# C8T6_MINI.net
KiCad netlist of a schematic drawn in Altium Designer
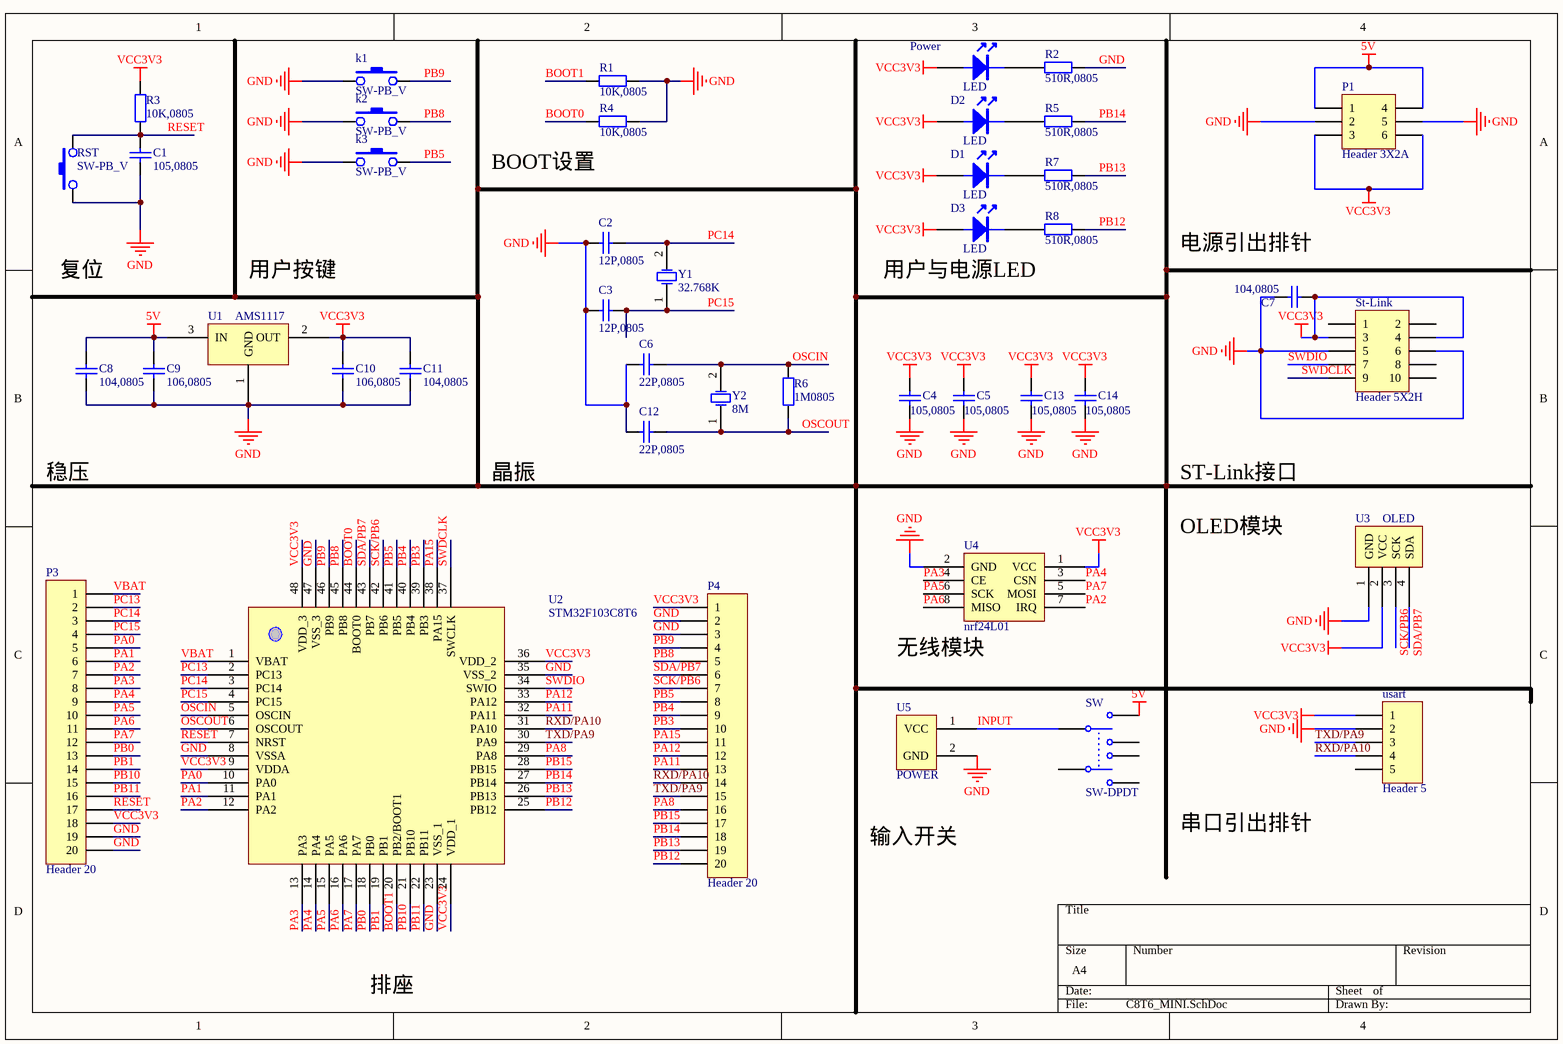
[diagram p0: C8T6_MINI.SchDoc]

(export (version "E")
  (design (tool "Eeschema 10.0.6"))
  (components
    (comp (ref "C1")
      (value "105,0805")
      (footprint "6-0805_M")
      (description "Capacitor")
      (fields (field (name "PUBLISHER") "Altium Limited"))
      (libsource (lib "STM32F103C8T6") (part "Cap"))
    )
    (comp (ref "C2")
      (value "12P,0805")
      (footprint "6-0805_N")
      (description "Capacitor")
      (fields (field (name "PUBLISHER") "Altium Limited"))
      (libsource (lib "stm32") (part "Cap_2"))
    )
    (comp (ref "C3")
      (value "12P,0805")
      (footprint "6-0805_N")
      (description "Capacitor")
      (fields (field (name "PUBLISHER") "Altium Limited"))
      (libsource (lib "stm32") (part "Cap_2"))
    )
    (comp (ref "C4")
      (value "105,0805")
      (footprint "6-0805_N")
      (description "Capacitor")
      (fields (field (name "PUBLISHER") "Altium Limited"))
      (libsource (lib "stm32") (part "Cap_2"))
    )
    (comp (ref "C5")
      (value "105,0805")
      (footprint "6-0805_N")
      (description "Capacitor")
      (fields (field (name "PUBLISHER") "Altium Limited"))
      (libsource (lib "stm32") (part "Cap_2"))
    )
    (comp (ref "C6")
      (value "22P,0805")
      (footprint "6-0805_N")
      (description "Capacitor")
      (fields (field (name "PUBLISHER") "Altium Limited"))
      (libsource (lib "stm32") (part "Cap_2"))
    )
    (comp (ref "C7")
      (value "104,0805")
      (footprint "6-0805_N")
      (description "Capacitor")
      (fields (field (name "PUBLISHER") "Altium Limited"))
      (libsource (lib "stm32") (part "Cap_2"))
    )
    (comp (ref "C8")
      (value "104,0805")
      (footprint "6-0805_N")
      (description "Capacitor")
      (fields (field (name "PUBLISHER") "Altium Limited"))
      (libsource (lib "stm32") (part "Cap_2"))
    )
    (comp (ref "C9")
      (value "106,0805")
      (footprint "6-0805_N")
      (description "Capacitor")
      (fields (field (name "PUBLISHER") "Altium Limited"))
      (libsource (lib "stm32") (part "Cap_2"))
    )
    (comp (ref "C10")
      (value "106,0805")
      (footprint "6-0805_N")
      (description "Capacitor")
      (fields (field (name "PUBLISHER") "Altium Limited"))
      (libsource (lib "stm32") (part "Cap_2"))
    )
    (comp (ref "C11")
      (value "104,0805")
      (footprint "6-0805_N")
      (description "Capacitor")
      (fields (field (name "PUBLISHER") "Altium Limited"))
      (libsource (lib "stm32") (part "Cap_2"))
    )
    (comp (ref "C12")
      (value "22P,0805")
      (footprint "6-0805_N")
      (description "Capacitor")
      (fields (field (name "PUBLISHER") "Altium Limited"))
      (libsource (lib "stm32") (part "Cap_2"))
    )
    (comp (ref "C13")
      (value "105,0805")
      (footprint "6-0805_N")
      (description "Capacitor")
      (fields (field (name "PUBLISHER") "Altium Limited"))
      (libsource (lib "stm32") (part "Cap_2"))
    )
    (comp (ref "C14")
      (value "105,0805")
      (footprint "6-0805_N")
      (description "Capacitor")
      (fields (field (name "PUBLISHER") "Altium Limited"))
      (libsource (lib "stm32") (part "Cap_2"))
    )
    (comp (ref "D1") (value "LED") (footprint "LED 0805G") (libsource (lib "STM32F103C8T6") (part "LED")))
    (comp (ref "D2") (value "LED") (footprint "LED 0805G") (libsource (lib "STM32F103C8T6") (part "LED")))
    (comp (ref "D3") (value "LED") (footprint "LED 0805G") (libsource (lib "STM32F103C8T6") (part "LED")))
    (comp (ref "k1")
      (value "SW-PB_V")
      (footprint "TSW SMD-3*6*2.5")
      (description "SWITCH")
      (libsource (lib "stm32") (part "SW-PB_V"))
    )
    (comp (ref "k2")
      (value "SW-PB_V")
      (footprint "TSW SMD-3*6*2.5")
      (description "SWITCH")
      (libsource (lib "stm32") (part "SW-PB_V"))
    )
    (comp (ref "k3")
      (value "SW-PB_V")
      (footprint "TSW SMD-3*6*2.5")
      (description "SWITCH")
      (libsource (lib "stm32") (part "SW-PB_V"))
    )
    (comp (ref "P1")
      (value "Header 3X2A")
      (footprint "HDR2X3_CEN")
      (description "Header, 3-Pin, Dual row")
      (fields (field (name "PUBLISHER") "Altium Limited"))
      (libsource (lib "Miscellaneous Connectors") (part "Header 3X2A"))
    )
    (comp (ref "P3")
      (value "Header 20")
      (footprint "HDR1X20")
      (description "Header, 20-Pin")
      (fields (field (name "PUBLISHER") "Altium Limited"))
      (libsource (lib "STM32F103C8T6") (part "Header 20"))
    )
    (comp (ref "P4")
      (value "Header 20")
      (footprint "HDR1X20")
      (description "Header, 20-Pin")
      (fields (field (name "PUBLISHER") "Altium Limited"))
      (libsource (lib "") (part "Header 20_1"))
    )
    (comp (ref "Power") (value "LED") (footprint "LED 0805G") (libsource (lib "STM32F103C8T6") (part "LED")))
    (comp (ref "R1")
      (value "10K,0805")
      (footprint "6-0805_N")
      (description "Resistor")
      (fields (field (name "PUBLISHER") "Altium Limited"))
      (libsource (lib "STM32F103C8T6") (part "Res2"))
    )
    (comp (ref "R2")
      (value "510R,0805")
      (footprint "6-0805_N")
      (description "Resistor")
      (fields (field (name "PUBLISHER") "Altium Limited"))
      (libsource (lib "STM32F103C8T6") (part "Res2"))
    )
    (comp (ref "R3")
      (value "10K,0805")
      (footprint "6-0805_N")
      (description "Resistor")
      (fields (field (name "PUBLISHER") "Altium Limited"))
      (libsource (lib "") (part "Res2_1"))
    )
    (comp (ref "R4")
      (value "10K,0805")
      (footprint "6-0805_N")
      (description "Resistor")
      (fields (field (name "PUBLISHER") "Altium Limited"))
      (libsource (lib "STM32F103C8T6") (part "Res2"))
    )
    (comp (ref "R5")
      (value "510R,0805")
      (footprint "6-0805_N")
      (description "Resistor")
      (fields (field (name "PUBLISHER") "Altium Limited"))
      (libsource (lib "STM32F103C8T6") (part "Res2"))
    )
    (comp (ref "R6")
      (value "1M0805")
      (footprint "6-0805_N")
      (description "Resistor")
      (fields (field (name "PUBLISHER") "Altium Limited"))
      (libsource (lib "") (part "Res2_1"))
    )
    (comp (ref "R7")
      (value "510R,0805")
      (footprint "6-0805_N")
      (description "Resistor")
      (fields (field (name "PUBLISHER") "Altium Limited"))
      (libsource (lib "STM32F103C8T6") (part "Res2"))
    )
    (comp (ref "R8")
      (value "510R,0805")
      (footprint "6-0805_N")
      (description "Resistor")
      (fields (field (name "PUBLISHER") "Altium Limited"))
      (libsource (lib "STM32F103C8T6") (part "Res2"))
    )
    (comp (ref "RST")
      (value "SW-PB_V")
      (footprint "TSW SMD-3*6*2.5")
      (description "SWITCH")
      (libsource (lib "STM32F103C8T6") (part "SW-PB_V"))
    )
    (comp (ref "St-Link")
      (value "Header 5X2H")
      (footprint "HDR2X5H")
      (description "Header, 5-Pin, Dual row, Right Angle")
      (fields (field (name "PUBLISHER") "Altium Limited"))
      (libsource (lib "Miscellaneous Connectors") (part "Header 5X2H"))
    )
    (comp (ref "SW")
      (value "SW-DPDT")
      (footprint "PCBComponent_1")
      (description "Double-Pole, Double-Throw Switch")
      (fields (field (name "PUBLISHER") "Altium Limited"))
      (libsource (lib "Miscellaneous Devices") (part "SW-DPDT"))
    )
    (comp (ref "U1")
      (value "AMS1117")
      (footprint "SOT223_M")
      (libsource (lib "AMS1117") (part "Component_1"))
    )
    (comp (ref "U2")
      (value "STM32F103C8T6")
      (footprint "TQFP48 7x7_L")
      (libsource (lib "stm32") (part "STM32F103C8T6"))
    )
    (comp (ref "U3") (value "OLED") (footprint "OLED") (libsource (lib "Schlib1") (part "oled")))
    (comp (ref "U4") (value "nrf24L01") (footprint "NRF24L01") (libsource (lib "Schlib1") (part "nrf24L01")))
    (comp (ref "U5") (value "POWER") (footprint "power") (libsource (lib "Schlib1") (part "POWER")))
    (comp (ref "usart")
      (value "Header 5")
      (footprint "HDR1X5")
      (description "Header, 5-Pin")
      (fields (field (name "PUBLISHER") "Altium Limited"))
      (libsource (lib "Miscellaneous Connectors") (part "Header 5"))
    )
    (comp (ref "Y1")
      (value "32.768K")
      (footprint "圆柱晶振")
      (description "Crystal Oscillator")
      (fields (field (name "PUBLISHER") "Altium Limited"))
      (libsource (lib "stm32") (part "XTAL_1"))
    )
    (comp (ref "Y2")
      (value "8M")
      (footprint "XTAL-49S DIP")
      (description "Crystal Oscillator")
      (fields (field (name "PUBLISHER") "Altium Limited"))
      (libsource (lib "STM32F103C8T6") (part "XTAL"))
    )
  )
  (nets
    (net (code "1") (name "/BOOT0") (class "Default")
      (node (ref "R4") (pin "1") (pinfunction "1_1") (pintype "passive"))
      (node (ref "U2") (pin "44") (pinfunction "BOOT0_44") (pintype "passive"))
    )
    (net (code "2") (name "/BOOT1") (class "Default")
      (node (ref "R1") (pin "1") (pinfunction "1_1") (pintype "passive"))
      (node (ref "U2") (pin "20") (pinfunction "PB2/BOOT1_20") (pintype "passive"))
    )
    (net (code "3") (name "/INPUT") (class "Default")
      (node (ref "SW") (pin "1") (pinfunction "1_1") (pintype "passive"))
      (node (ref "U5") (pin "1") (pinfunction "VCC_1") (pintype "passive"))
    )
    (net (code "4") (name "/OSCIN") (class "Default")
      (node (ref "C6") (pin "1") (pinfunction "1_1") (pintype "passive"))
      (node (ref "R6") (pin "2") (pinfunction "2_2") (pintype "passive"))
      (node (ref "U2") (pin "5") (pinfunction "OSCIN_5") (pintype "passive"))
      (node (ref "Y2") (pin "2") (pinfunction "OSC2_2") (pintype "passive"))
    )
    (net (code "5") (name "/OSCOUT") (class "Default")
      (node (ref "C12") (pin "1") (pinfunction "1_1") (pintype "passive"))
      (node (ref "R6") (pin "1") (pinfunction "1_1") (pintype "passive"))
      (node (ref "U2") (pin "6") (pinfunction "OSCOUT_6") (pintype "passive"))
      (node (ref "Y2") (pin "1") (pinfunction "OSC1_1") (pintype "passive"))
    )
    (net (code "6") (name "/PA0") (class "Default")
      (node (ref "P3") (pin "5") (pinfunction "5_5") (pintype "passive"))
      (node (ref "U2") (pin "10") (pinfunction "PA0_10") (pintype "passive"))
    )
    (net (code "7") (name "/PA1") (class "Default")
      (node (ref "P3") (pin "6") (pinfunction "6_6") (pintype "passive"))
      (node (ref "U2") (pin "11") (pinfunction "PA1_11") (pintype "passive"))
    )
    (net (code "8") (name "/PA2") (class "Default")
      (node (ref "P3") (pin "7") (pinfunction "7_7") (pintype "passive"))
      (node (ref "U2") (pin "12") (pinfunction "PA2_12") (pintype "passive"))
      (node (ref "U4") (pin "7") (pinfunction "IRQ_7") (pintype "passive"))
    )
    (net (code "9") (name "/PA3") (class "Default")
      (node (ref "P3") (pin "8") (pinfunction "8_8") (pintype "passive"))
      (node (ref "U2") (pin "13") (pinfunction "PA3_13") (pintype "passive"))
      (node (ref "U4") (pin "4") (pinfunction "CE_4") (pintype "passive"))
    )
    (net (code "10") (name "/PA4") (class "Default")
      (node (ref "P3") (pin "9") (pinfunction "9_9") (pintype "passive"))
      (node (ref "U2") (pin "14") (pinfunction "PA4_14") (pintype "passive"))
      (node (ref "U4") (pin "3") (pinfunction "CSN_3") (pintype "passive"))
    )
    (net (code "11") (name "/PA5") (class "Default")
      (node (ref "P3") (pin "10") (pinfunction "10_10") (pintype "passive"))
      (node (ref "U2") (pin "15") (pinfunction "PA5_15") (pintype "passive"))
      (node (ref "U4") (pin "6") (pinfunction "SCK_6") (pintype "passive"))
    )
    (net (code "12") (name "/PA6") (class "Default")
      (node (ref "P3") (pin "11") (pinfunction "11_11") (pintype "passive"))
      (node (ref "U2") (pin "16") (pinfunction "PA6_16") (pintype "passive"))
      (node (ref "U4") (pin "8") (pinfunction "MISO_8") (pintype "passive"))
    )
    (net (code "13") (name "/PA7") (class "Default")
      (node (ref "P3") (pin "12") (pinfunction "12_12") (pintype "passive"))
      (node (ref "U2") (pin "17") (pinfunction "PA7_17") (pintype "passive"))
      (node (ref "U4") (pin "5") (pinfunction "MOSI_5") (pintype "passive"))
    )
    (net (code "14") (name "/PA8") (class "Default")
      (node (ref "P4") (pin "16") (pinfunction "16_16") (pintype "passive"))
      (node (ref "U2") (pin "29") (pinfunction "PA8_29") (pintype "passive"))
    )
    (net (code "15") (name "/PA11") (class "Default")
      (node (ref "P4") (pin "13") (pinfunction "13_13") (pintype "passive"))
      (node (ref "U2") (pin "32") (pinfunction "PA11_32") (pintype "passive"))
    )
    (net (code "16") (name "/PA12") (class "Default")
      (node (ref "P4") (pin "12") (pinfunction "12_12") (pintype "passive"))
      (node (ref "U2") (pin "33") (pinfunction "PA12_33") (pintype "passive"))
    )
    (net (code "17") (name "/PA15") (class "Default")
      (node (ref "P4") (pin "11") (pinfunction "11_11") (pintype "passive"))
      (node (ref "U2") (pin "38") (pinfunction "PA15_38") (pintype "passive"))
    )
    (net (code "18") (name "/PB0") (class "Default")
      (node (ref "P3") (pin "13") (pinfunction "13_13") (pintype "passive"))
      (node (ref "U2") (pin "18") (pinfunction "PB0_18") (pintype "passive"))
    )
    (net (code "19") (name "/PB1") (class "Default")
      (node (ref "P3") (pin "14") (pinfunction "14_14") (pintype "passive"))
      (node (ref "U2") (pin "19") (pinfunction "PB1_19") (pintype "passive"))
    )
    (net (code "20") (name "/PB3") (class "Default")
      (node (ref "P4") (pin "10") (pinfunction "10_10") (pintype "passive"))
      (node (ref "U2") (pin "39") (pinfunction "PB3_39") (pintype "passive"))
    )
    (net (code "21") (name "/PB4") (class "Default")
      (node (ref "P4") (pin "9") (pinfunction "9_9") (pintype "passive"))
      (node (ref "U2") (pin "40") (pinfunction "PB4_40") (pintype "passive"))
    )
    (net (code "22") (name "/PB5") (class "Default")
      (node (ref "P4") (pin "8") (pinfunction "8_8") (pintype "passive"))
      (node (ref "U2") (pin "41") (pinfunction "PB5_41") (pintype "passive"))
      (node (ref "k3") (pin "2") (pinfunction "2_2") (pintype "passive"))
    )
    (net (code "23") (name "/PB8") (class "Default")
      (node (ref "P4") (pin "5") (pinfunction "5_5") (pintype "passive"))
      (node (ref "U2") (pin "45") (pinfunction "PB8_45") (pintype "passive"))
      (node (ref "k2") (pin "2") (pinfunction "2_2") (pintype "passive"))
    )
    (net (code "24") (name "/PB9") (class "Default")
      (node (ref "P4") (pin "4") (pinfunction "4_4") (pintype "passive"))
      (node (ref "U2") (pin "46") (pinfunction "PB9_46") (pintype "passive"))
      (node (ref "k1") (pin "2") (pinfunction "2_2") (pintype "passive"))
    )
    (net (code "25") (name "/PB10") (class "Default")
      (node (ref "P3") (pin "15") (pinfunction "15_15") (pintype "passive"))
      (node (ref "U2") (pin "21") (pinfunction "PB10_21") (pintype "passive"))
    )
    (net (code "26") (name "/PB11") (class "Default")
      (node (ref "P3") (pin "16") (pinfunction "16_16") (pintype "passive"))
      (node (ref "U2") (pin "22") (pinfunction "PB11_22") (pintype "passive"))
    )
    (net (code "27") (name "/PB12") (class "Default")
      (node (ref "P4") (pin "20") (pinfunction "20_20") (pintype "passive"))
      (node (ref "R8") (pin "2") (pinfunction "2_2") (pintype "passive"))
      (node (ref "U2") (pin "25") (pinfunction "PB12_25") (pintype "passive"))
    )
    (net (code "28") (name "/PB13") (class "Default")
      (node (ref "P4") (pin "19") (pinfunction "19_19") (pintype "passive"))
      (node (ref "R7") (pin "2") (pinfunction "2_2") (pintype "passive"))
      (node (ref "U2") (pin "26") (pinfunction "PB13_26") (pintype "passive"))
    )
    (net (code "29") (name "/PB14") (class "Default")
      (node (ref "P4") (pin "18") (pinfunction "18_18") (pintype "passive"))
      (node (ref "R5") (pin "2") (pinfunction "2_2") (pintype "passive"))
      (node (ref "U2") (pin "27") (pinfunction "PB14_27") (pintype "passive"))
    )
    (net (code "30") (name "/PB15") (class "Default")
      (node (ref "P4") (pin "17") (pinfunction "17_17") (pintype "passive"))
      (node (ref "U2") (pin "28") (pinfunction "PB15_28") (pintype "passive"))
    )
    (net (code "31") (name "/PC13") (class "Default")
      (node (ref "P3") (pin "2") (pinfunction "2_2") (pintype "passive"))
      (node (ref "U2") (pin "2") (pinfunction "PC13_2") (pintype "passive"))
    )
    (net (code "32") (name "/PC14") (class "Default")
      (node (ref "C2") (pin "1") (pinfunction "1_1") (pintype "passive"))
      (node (ref "P3") (pin "3") (pinfunction "3_3") (pintype "passive"))
      (node (ref "U2") (pin "3") (pinfunction "PC14_3") (pintype "passive"))
      (node (ref "Y1") (pin "2") (pinfunction "OSC2_2") (pintype "passive"))
    )
    (net (code "33") (name "/PC15") (class "Default")
      (node (ref "C3") (pin "1") (pinfunction "1_1") (pintype "passive"))
      (node (ref "P3") (pin "4") (pinfunction "4_4") (pintype "passive"))
      (node (ref "U2") (pin "4") (pinfunction "PC15_4") (pintype "passive"))
      (node (ref "Y1") (pin "1") (pinfunction "OSC1_1") (pintype "passive"))
    )
    (net (code "34") (name "/RESET") (class "Default")
      (node (ref "C1") (pin "2") (pinfunction "2_2") (pintype "passive"))
      (node (ref "P3") (pin "17") (pinfunction "17_17") (pintype "passive"))
      (node (ref "R3") (pin "1") (pinfunction "1_1") (pintype "passive"))
      (node (ref "RST") (pin "2") (pinfunction "2_2") (pintype "passive"))
      (node (ref "U2") (pin "7") (pinfunction "NRST_7") (pintype "passive"))
    )
    (net (code "35") (name "/RXD{slash}PA10") (class "Default")
      (node (ref "P4") (pin "14") (pinfunction "14_14") (pintype "passive"))
      (node (ref "U2") (pin "31") (pinfunction "PA10_31") (pintype "passive"))
      (node (ref "usart") (pin "4") (pinfunction "4_4") (pintype "passive"))
    )
    (net (code "36") (name "/SCK{slash}PB6") (class "Default")
      (node (ref "P4") (pin "7") (pinfunction "7_7") (pintype "passive"))
      (node (ref "U2") (pin "42") (pinfunction "PB6_42") (pintype "passive"))
      (node (ref "U3") (pin "3") (pinfunction "SCK_3") (pintype "passive"))
    )
    (net (code "37") (name "/SDA{slash}PB7") (class "Default")
      (node (ref "P4") (pin "6") (pinfunction "6_6") (pintype "passive"))
      (node (ref "U2") (pin "43") (pinfunction "PB7_43") (pintype "passive"))
      (node (ref "U3") (pin "4") (pinfunction "SDA_4") (pintype "passive"))
    )
    (net (code "38") (name "/SWDCLK") (class "Default")
      (node (ref "St-Link") (pin "9") (pinfunction "9_9") (pintype "passive"))
      (node (ref "U2") (pin "37") (pinfunction "SWCLK_37") (pintype "passive"))
    )
    (net (code "39") (name "/SWDIO") (class "Default")
      (node (ref "St-Link") (pin "7") (pinfunction "7_7") (pintype "passive"))
      (node (ref "U2") (pin "34") (pinfunction "SWIO_34") (pintype "passive"))
    )
    (net (code "40") (name "/TXD{slash}PA9") (class "Default")
      (node (ref "P4") (pin "15") (pinfunction "15_15") (pintype "passive"))
      (node (ref "U2") (pin "30") (pinfunction "PA9_30") (pintype "passive"))
      (node (ref "usart") (pin "3") (pinfunction "3_3") (pintype "passive"))
    )
    (net (code "41") (name "/VBAT") (class "Default")
      (node (ref "P3") (pin "1") (pinfunction "1_1") (pintype "passive"))
      (node (ref "U2") (pin "1") (pinfunction "VBAT_1") (pintype "passive"))
    )
    (net (code "42") (name "5V") (class "Default")
      (node (ref "C8") (pin "1") (pinfunction "1_1") (pintype "passive"))
      (node (ref "C9") (pin "1") (pinfunction "1_1") (pintype "passive"))
      (node (ref "P1") (pin "1") (pinfunction "1_1") (pintype "passive"))
      (node (ref "P1") (pin "4") (pinfunction "4_4") (pintype "passive"))
      (node (ref "SW") (pin "2") (pinfunction "2_2") (pintype "passive"))
      (node (ref "U1") (pin "3") (pinfunction "IN_3") (pintype "passive"))
    )
    (net (code "43") (name "GND") (class "Default")
      (node (ref "C1") (pin "1") (pinfunction "1_1") (pintype "passive"))
      (node (ref "C10") (pin "1") (pinfunction "1_1") (pintype "passive"))
      (node (ref "C11") (pin "1") (pinfunction "1_1") (pintype "passive"))
      (node (ref "C12") (pin "2") (pinfunction "2_2") (pintype "passive"))
      (node (ref "C13") (pin "1") (pinfunction "1_1") (pintype "passive"))
      (node (ref "C14") (pin "1") (pinfunction "1_1") (pintype "passive"))
      (node (ref "C2") (pin "2") (pinfunction "2_2") (pintype "passive"))
      (node (ref "C3") (pin "2") (pinfunction "2_2") (pintype "passive"))
      (node (ref "C4") (pin "1") (pinfunction "1_1") (pintype "passive"))
      (node (ref "C5") (pin "1") (pinfunction "1_1") (pintype "passive"))
      (node (ref "C6") (pin "2") (pinfunction "2_2") (pintype "passive"))
      (node (ref "C7") (pin "2") (pinfunction "2_2") (pintype "passive"))
      (node (ref "C8") (pin "2") (pinfunction "2_2") (pintype "passive"))
      (node (ref "C9") (pin "2") (pinfunction "2_2") (pintype "passive"))
      (node (ref "P1") (pin "2") (pinfunction "2_2") (pintype "passive"))
      (node (ref "P1") (pin "5") (pinfunction "5_5") (pintype "passive"))
      (node (ref "P3") (pin "19") (pinfunction "19_19") (pintype "passive"))
      (node (ref "P3") (pin "20") (pinfunction "20_20") (pintype "passive"))
      (node (ref "P4") (pin "2") (pinfunction "2_2") (pintype "passive"))
      (node (ref "P4") (pin "3") (pinfunction "3_3") (pintype "passive"))
      (node (ref "R1") (pin "2") (pinfunction "2_2") (pintype "passive"))
      (node (ref "R2") (pin "2") (pinfunction "2_2") (pintype "passive"))
      (node (ref "R4") (pin "2") (pinfunction "2_2") (pintype "passive"))
      (node (ref "RST") (pin "1") (pinfunction "1_1") (pintype "passive"))
      (node (ref "St-Link") (pin "5") (pinfunction "5_5") (pintype "passive"))
      (node (ref "St-Link") (pin "6") (pinfunction "6_6") (pintype "passive"))
      (node (ref "U1") (pin "1") (pinfunction "GND_1") (pintype "passive"))
      (node (ref "U2") (pin "23") (pinfunction "VSS_1_23") (pintype "passive"))
      (node (ref "U2") (pin "35") (pinfunction "VSS_2_35") (pintype "passive"))
      (node (ref "U2") (pin "47") (pinfunction "VSS_3_47") (pintype "passive"))
      (node (ref "U2") (pin "8") (pinfunction "VSSA_8") (pintype "passive"))
      (node (ref "U3") (pin "1") (pinfunction "GND_1") (pintype "passive"))
      (node (ref "U4") (pin "2") (pinfunction "GND_2") (pintype "passive"))
      (node (ref "U5") (pin "2") (pinfunction "GND_2") (pintype "passive"))
      (node (ref "k1") (pin "1") (pinfunction "1_1") (pintype "passive"))
      (node (ref "k2") (pin "1") (pinfunction "1_1") (pintype "passive"))
      (node (ref "k3") (pin "1") (pinfunction "1_1") (pintype "passive"))
      (node (ref "usart") (pin "2") (pinfunction "2_2") (pintype "passive"))
    )
    (net (code "44") (name "Net-(D1-Pad2)") (class "Default")
      (node (ref "D1") (pin "2") (pinfunction "2_2") (pintype "passive"))
      (node (ref "R7") (pin "1") (pinfunction "1_1") (pintype "passive"))
    )
    (net (code "45") (name "Net-(D2-Pad2)") (class "Default")
      (node (ref "D2") (pin "2") (pinfunction "2_2") (pintype "passive"))
      (node (ref "R5") (pin "1") (pinfunction "1_1") (pintype "passive"))
    )
    (net (code "46") (name "Net-(D3-Pad2)") (class "Default")
      (node (ref "D3") (pin "2") (pinfunction "2_2") (pintype "passive"))
      (node (ref "R8") (pin "1") (pinfunction "1_1") (pintype "passive"))
    )
    (net (code "47") (name "Net-(Power-Pad2)") (class "Default")
      (node (ref "Power") (pin "2") (pinfunction "2_2") (pintype "passive"))
      (node (ref "R2") (pin "1") (pinfunction "1_1") (pintype "passive"))
    )
    (net (code "48") (name "VCC3V3") (class "Default")
      (node (ref "C10") (pin "2") (pinfunction "2_2") (pintype "passive"))
      (node (ref "C11") (pin "2") (pinfunction "2_2") (pintype "passive"))
      (node (ref "C13") (pin "2") (pinfunction "2_2") (pintype "passive"))
      (node (ref "C14") (pin "2") (pinfunction "2_2") (pintype "passive"))
      (node (ref "C4") (pin "2") (pinfunction "2_2") (pintype "passive"))
      (node (ref "C5") (pin "2") (pinfunction "2_2") (pintype "passive"))
      (node (ref "C7") (pin "1") (pinfunction "1_1") (pintype "passive"))
      (node (ref "D1") (pin "1") (pinfunction "1_1") (pintype "passive"))
      (node (ref "D2") (pin "1") (pinfunction "1_1") (pintype "passive"))
      (node (ref "D3") (pin "1") (pinfunction "1_1") (pintype "passive"))
      (node (ref "P1") (pin "3") (pinfunction "3_3") (pintype "passive"))
      (node (ref "P1") (pin "6") (pinfunction "6_6") (pintype "passive"))
      (node (ref "P3") (pin "18") (pinfunction "18_18") (pintype "passive"))
      (node (ref "P4") (pin "1") (pinfunction "1_1") (pintype "passive"))
      (node (ref "Power") (pin "1") (pinfunction "1_1") (pintype "passive"))
      (node (ref "R3") (pin "2") (pinfunction "2_2") (pintype "passive"))
      (node (ref "St-Link") (pin "3") (pinfunction "3_3") (pintype "passive"))
      (node (ref "St-Link") (pin "4") (pinfunction "4_4") (pintype "passive"))
      (node (ref "U1") (pin "2") (pinfunction "OUT_2") (pintype "passive"))
      (node (ref "U2") (pin "24") (pinfunction "VDD_1_24") (pintype "passive"))
      (node (ref "U2") (pin "36") (pinfunction "VDD_2_36") (pintype "passive"))
      (node (ref "U2") (pin "48") (pinfunction "VDD_3_48") (pintype "passive"))
      (node (ref "U2") (pin "9") (pinfunction "VDDA_9") (pintype "passive"))
      (node (ref "U3") (pin "2") (pinfunction "VCC_2") (pintype "passive"))
      (node (ref "U4") (pin "1") (pinfunction "VCC_1") (pintype "passive"))
      (node (ref "usart") (pin "1") (pinfunction "1_1") (pintype "passive"))
    )
    (net (code "49") (name "unconnected-(SW-Pad3)") (class "Default")
      (node (ref "SW") (pin "3") (pinfunction "3_3") (pintype "passive"))
    )
    (net (code "50") (name "unconnected-(SW-Pad4)") (class "Default")
      (node (ref "SW") (pin "4") (pinfunction "4_4") (pintype "passive"))
    )
    (net (code "51") (name "unconnected-(SW-Pad5)") (class "Default")
      (node (ref "SW") (pin "5") (pinfunction "5_5") (pintype "passive"))
    )
    (net (code "52") (name "unconnected-(SW-Pad6)") (class "Default")
      (node (ref "SW") (pin "6") (pinfunction "6_6") (pintype "passive"))
    )
    (net (code "53") (name "unconnected-(St-Link-Pad1)") (class "Default")
      (node (ref "St-Link") (pin "1") (pinfunction "1_1") (pintype "passive"))
    )
    (net (code "54") (name "unconnected-(St-Link-Pad2)") (class "Default")
      (node (ref "St-Link") (pin "2") (pinfunction "2_2") (pintype "passive"))
    )
    (net (code "55") (name "unconnected-(St-Link-Pad8)") (class "Default")
      (node (ref "St-Link") (pin "8") (pinfunction "8_8") (pintype "passive"))
    )
    (net (code "56") (name "unconnected-(St-Link-Pad10)") (class "Default")
      (node (ref "St-Link") (pin "10") (pinfunction "10_10") (pintype "passive"))
    )
    (net (code "57") (name "unconnected-(usart-Pad5)") (class "Default")
      (node (ref "usart") (pin "5") (pinfunction "5_5") (pintype "passive"))
    )
  )
)
